# usb-fanctl.net
KiCad netlist of a schematic drawn in EAGLE
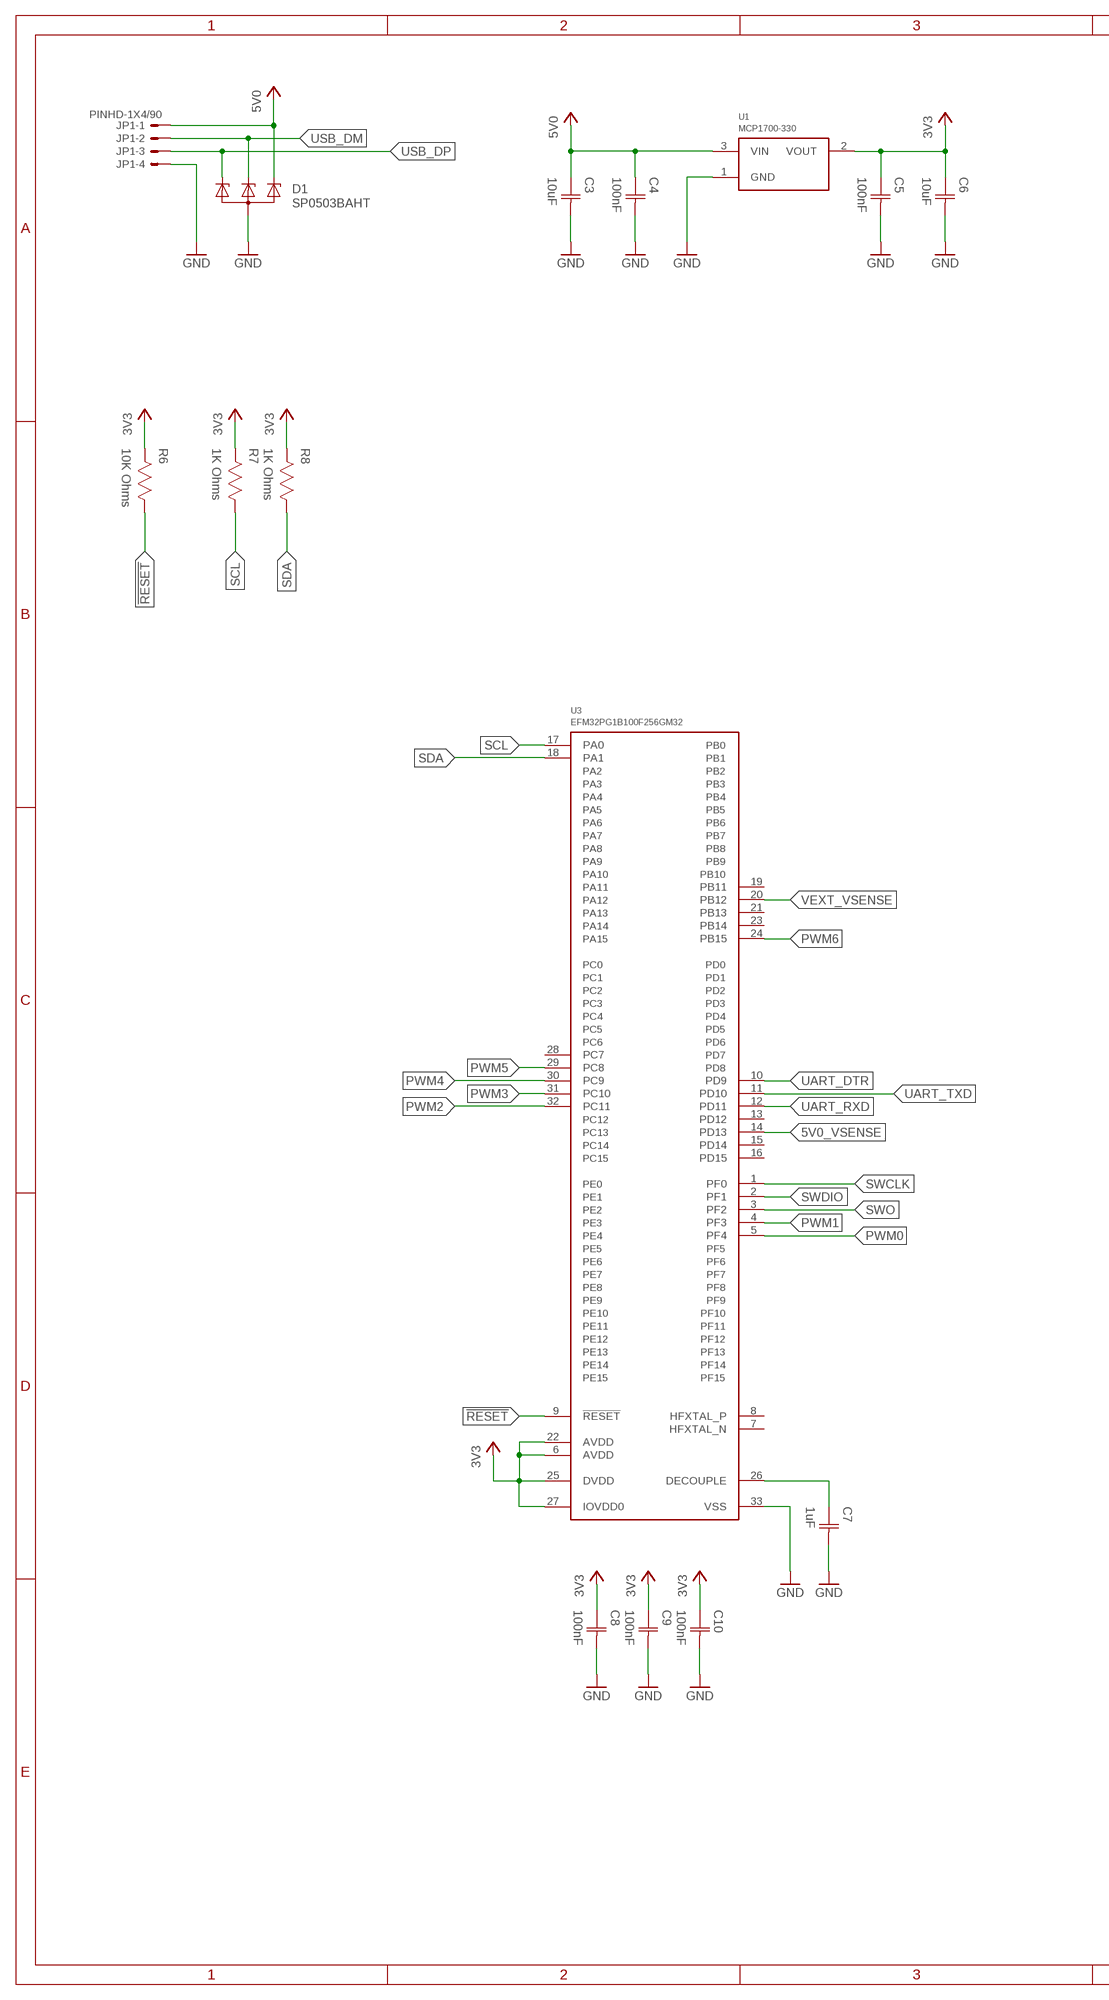
[diagram p0: schematic, sheet 1, part 1 of 2]
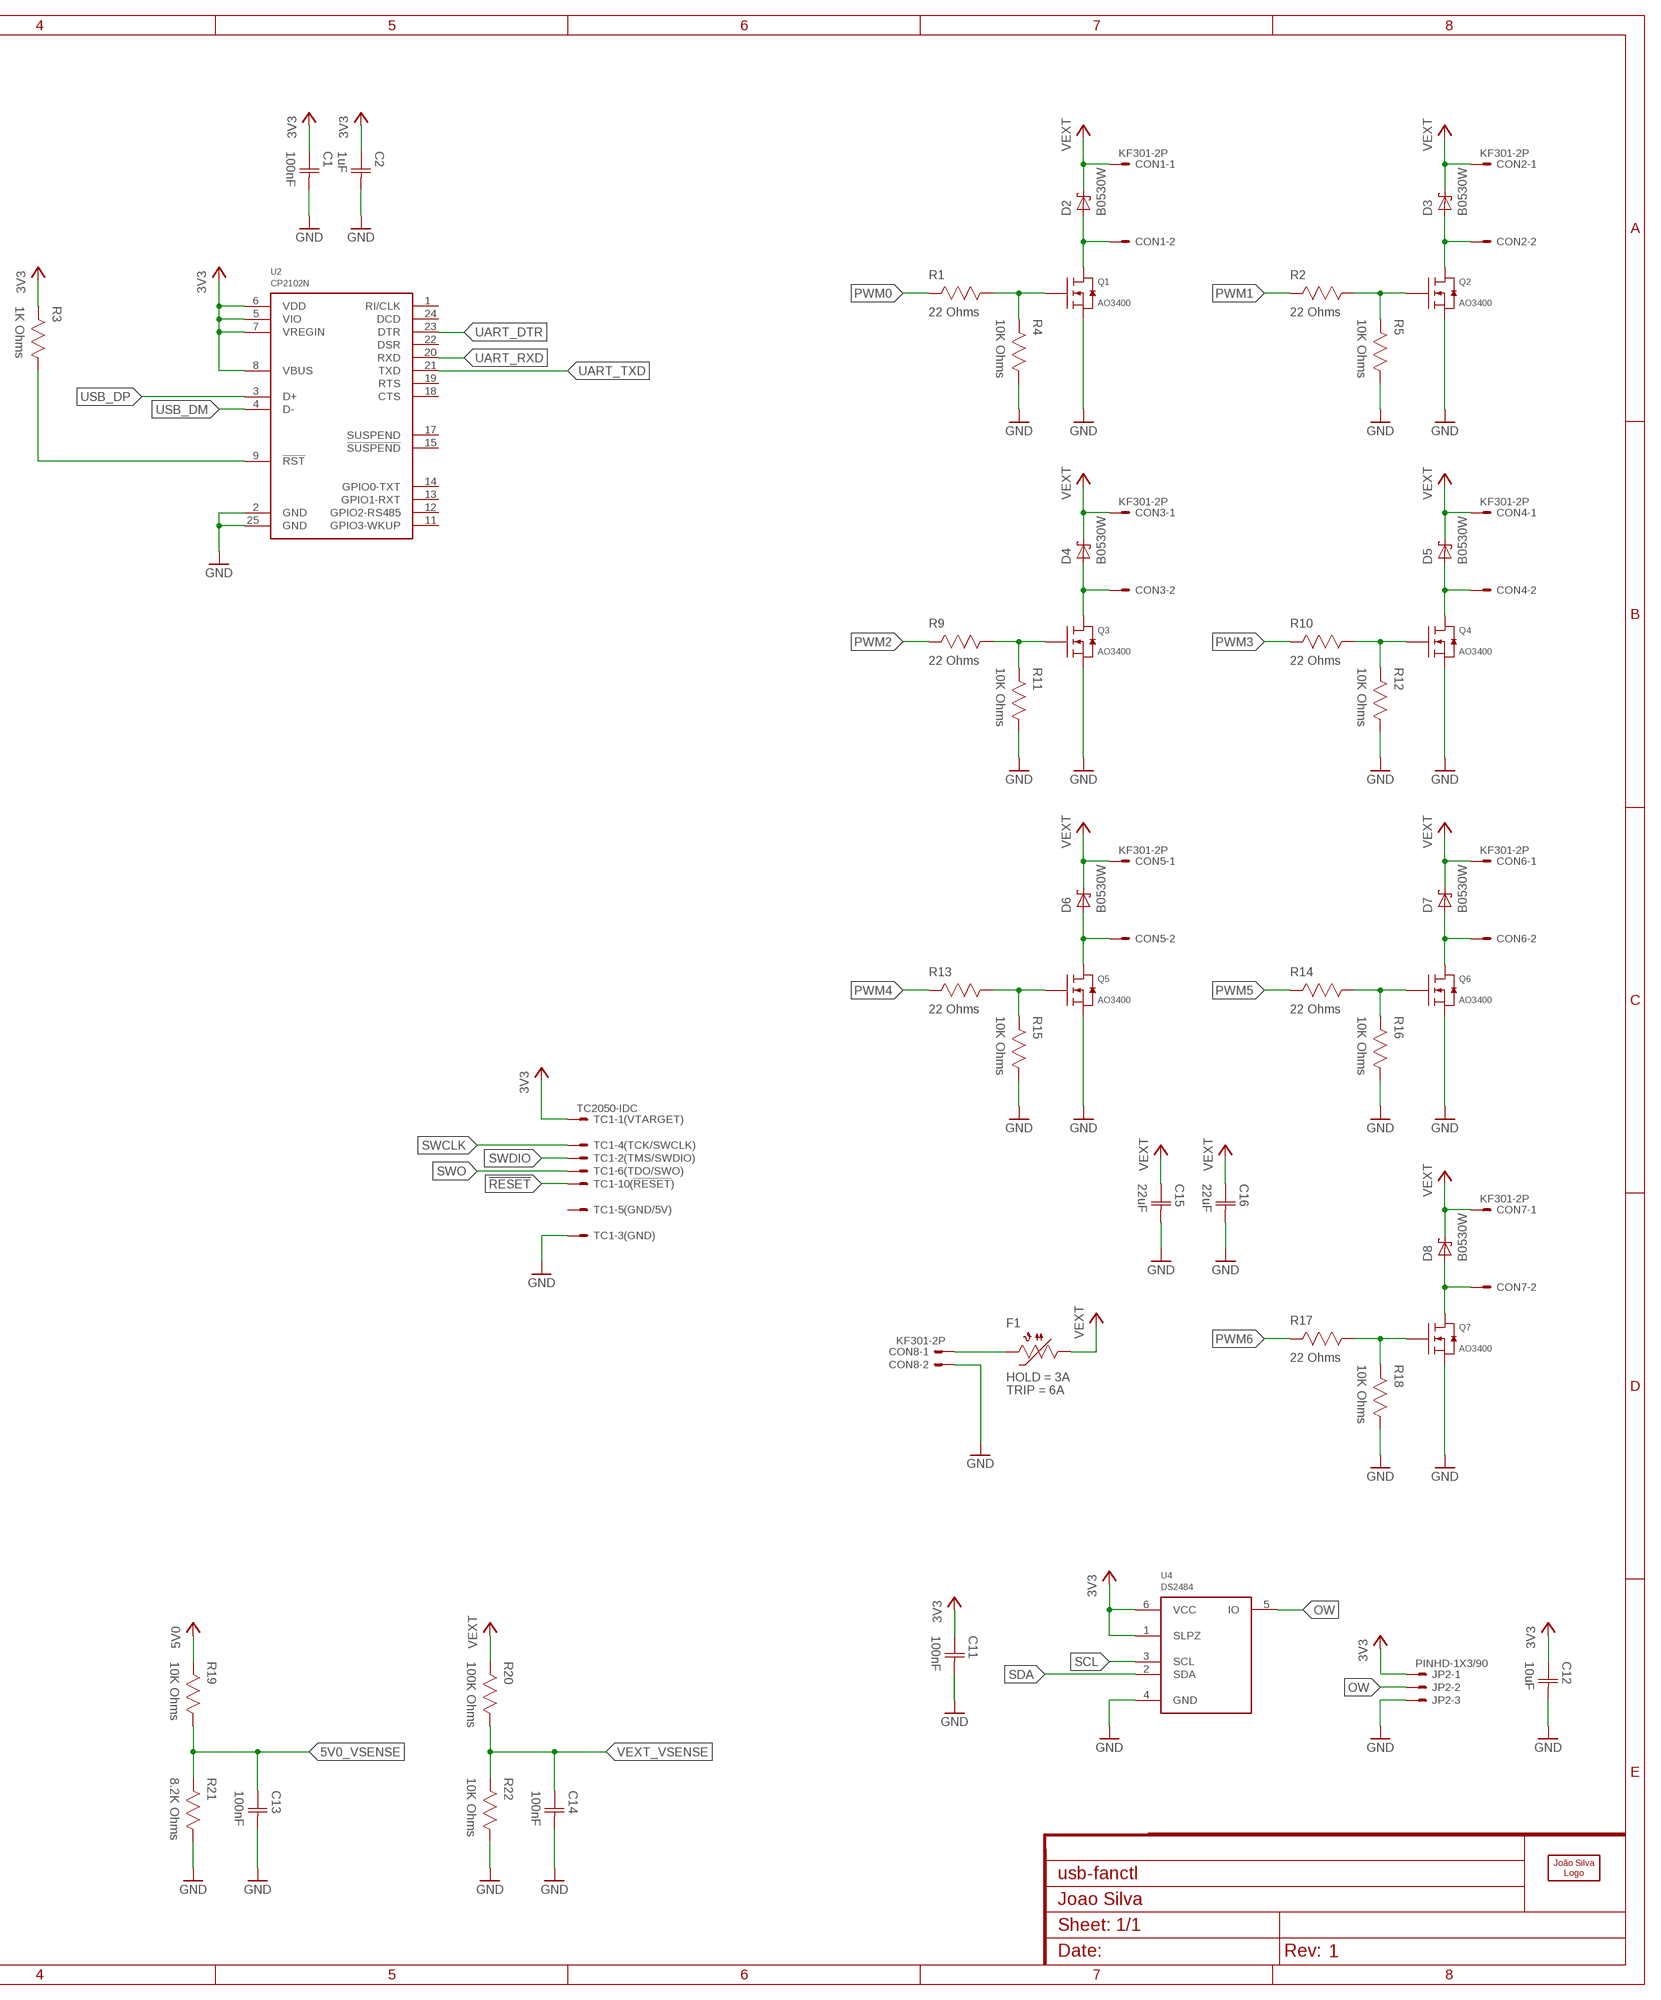
[diagram p1: schematic, sheet 1, part 2 of 2]

(export (version "E")
  (design (tool "Eeschema 10.0.6"))
  (components
    (comp (ref "C1")
      (value "100nF")
      (footprint "eagle-import:CAP0402")
      (libsource (lib "eagle-import") (part "CAPACITOR-0402"))
    )
    (comp (ref "C2")
      (value "1uF")
      (footprint "eagle-import:CAP0402")
      (libsource (lib "eagle-import") (part "CAPACITOR-0402"))
    )
    (comp (ref "C3")
      (value "10uF")
      (footprint "eagle-import:CAP0603")
      (libsource (lib "eagle-import") (part "CAPACITOR-0603"))
    )
    (comp (ref "C4")
      (value "100nF")
      (footprint "eagle-import:CAP0402")
      (libsource (lib "eagle-import") (part "CAPACITOR-0402"))
    )
    (comp (ref "C5")
      (value "100nF")
      (footprint "eagle-import:CAP0402")
      (libsource (lib "eagle-import") (part "CAPACITOR-0402"))
    )
    (comp (ref "C6")
      (value "10uF")
      (footprint "eagle-import:CAP0603")
      (libsource (lib "eagle-import") (part "CAPACITOR-0603"))
    )
    (comp (ref "C7")
      (value "1uF")
      (footprint "eagle-import:CAP0402")
      (libsource (lib "eagle-import") (part "CAPACITOR-0402"))
    )
    (comp (ref "C8")
      (value "100nF")
      (footprint "eagle-import:CAP0402")
      (libsource (lib "eagle-import") (part "CAPACITOR-0402"))
    )
    (comp (ref "C9")
      (value "100nF")
      (footprint "eagle-import:CAP0402")
      (libsource (lib "eagle-import") (part "CAPACITOR-0402"))
    )
    (comp (ref "C10")
      (value "100nF")
      (footprint "eagle-import:CAP0402")
      (libsource (lib "eagle-import") (part "CAPACITOR-0402"))
    )
    (comp (ref "C11")
      (value "100nF")
      (footprint "eagle-import:CAP0402")
      (libsource (lib "eagle-import") (part "CAPACITOR-0402"))
    )
    (comp (ref "C12")
      (value "10uF")
      (footprint "eagle-import:CAP0603")
      (libsource (lib "eagle-import") (part "CAPACITOR-0603"))
    )
    (comp (ref "C13")
      (value "100nF")
      (footprint "eagle-import:CAP0402")
      (libsource (lib "eagle-import") (part "CAPACITOR-0402"))
    )
    (comp (ref "C14")
      (value "100nF")
      (footprint "eagle-import:CAP0402")
      (libsource (lib "eagle-import") (part "CAPACITOR-0402"))
    )
    (comp (ref "C15")
      (value "22uF")
      (footprint "eagle-import:CAP1206")
      (libsource (lib "eagle-import") (part "CAPACITOR-1206"))
    )
    (comp (ref "C16")
      (value "22uF")
      (footprint "eagle-import:CAP1206")
      (libsource (lib "eagle-import") (part "CAPACITOR-1206"))
    )
    (comp (ref "CON1")
      (value "KF301-2P")
      (footprint "eagle-import:KF301-2P")
      (libsource (lib "eagle-import") (part "KF301-2P"))
    )
    (comp (ref "CON2")
      (value "KF301-2P")
      (footprint "eagle-import:KF301-2P")
      (libsource (lib "eagle-import") (part "KF301-2P"))
    )
    (comp (ref "CON3")
      (value "KF301-2P")
      (footprint "eagle-import:KF301-2P")
      (libsource (lib "eagle-import") (part "KF301-2P"))
    )
    (comp (ref "CON4")
      (value "KF301-2P")
      (footprint "eagle-import:KF301-2P")
      (libsource (lib "eagle-import") (part "KF301-2P"))
    )
    (comp (ref "CON5")
      (value "KF301-2P")
      (footprint "eagle-import:KF301-2P")
      (libsource (lib "eagle-import") (part "KF301-2P"))
    )
    (comp (ref "CON6")
      (value "KF301-2P")
      (footprint "eagle-import:KF301-2P")
      (libsource (lib "eagle-import") (part "KF301-2P"))
    )
    (comp (ref "CON7")
      (value "KF301-2P")
      (footprint "eagle-import:KF301-2P")
      (libsource (lib "eagle-import") (part "KF301-2P"))
    )
    (comp (ref "CON8")
      (value "KF301-2P")
      (footprint "eagle-import:KF301-2P")
      (libsource (lib "eagle-import") (part "KF301-2P"))
    )
    (comp (ref "D1")
      (value "SP0503BAHT")
      (footprint "eagle-import:SOT143")
      (libsource (lib "eagle-import") (part "SP0503BAHT"))
    )
    (comp (ref "D2")
      (value "B0530W")
      (footprint "eagle-import:SOD-123")
      (libsource (lib "eagle-import") (part "B0530W"))
    )
    (comp (ref "D3")
      (value "B0530W")
      (footprint "eagle-import:SOD-123")
      (libsource (lib "eagle-import") (part "B0530W"))
    )
    (comp (ref "D4")
      (value "B0530W")
      (footprint "eagle-import:SOD-123")
      (libsource (lib "eagle-import") (part "B0530W"))
    )
    (comp (ref "D5")
      (value "B0530W")
      (footprint "eagle-import:SOD-123")
      (libsource (lib "eagle-import") (part "B0530W"))
    )
    (comp (ref "D6")
      (value "B0530W")
      (footprint "eagle-import:SOD-123")
      (libsource (lib "eagle-import") (part "B0530W"))
    )
    (comp (ref "D7")
      (value "B0530W")
      (footprint "eagle-import:SOD-123")
      (libsource (lib "eagle-import") (part "B0530W"))
    )
    (comp (ref "D8")
      (value "B0530W")
      (footprint "eagle-import:SOD-123")
      (libsource (lib "eagle-import") (part "B0530W"))
    )
    (comp (ref "F1")
      (value "PTC1206")
      (footprint "eagle-import:1206")
      (fields (field (name "HOLD") "3A") (field (name "TRIP") "6A"))
      (libsource (lib "eagle-import") (part "PTC1206"))
    )
    (comp (ref "JP1")
      (value "PINHD-1X4/90")
      (footprint "eagle-import:1X04_90")
      (libsource (lib "eagle-import") (part "PINHD-1X4/90"))
    )
    (comp (ref "JP2")
      (value "PINHD-1X3/90")
      (footprint "eagle-import:1X03_90")
      (libsource (lib "eagle-import") (part "PINHD-1X3/90"))
    )
    (comp (ref "LOGO1")
      (value "JS-5MM")
      (footprint "eagle-import:JS_5MM")
      (libsource (lib "eagle-import") (part "JS-5MM"))
    )
    (comp (ref "Q1")
      (value "AO3400")
      (footprint "eagle-import:SOT23")
      (libsource (lib "eagle-import") (part "AO3400"))
    )
    (comp (ref "Q2")
      (value "AO3400")
      (footprint "eagle-import:SOT23")
      (libsource (lib "eagle-import") (part "AO3400"))
    )
    (comp (ref "Q3")
      (value "AO3400")
      (footprint "eagle-import:SOT23")
      (libsource (lib "eagle-import") (part "AO3400"))
    )
    (comp (ref "Q4")
      (value "AO3400")
      (footprint "eagle-import:SOT23")
      (libsource (lib "eagle-import") (part "AO3400"))
    )
    (comp (ref "Q5")
      (value "AO3400")
      (footprint "eagle-import:SOT23")
      (libsource (lib "eagle-import") (part "AO3400"))
    )
    (comp (ref "Q6")
      (value "AO3400")
      (footprint "eagle-import:SOT23")
      (libsource (lib "eagle-import") (part "AO3400"))
    )
    (comp (ref "Q7")
      (value "AO3400")
      (footprint "eagle-import:SOT23")
      (libsource (lib "eagle-import") (part "AO3400"))
    )
    (comp (ref "R1")
      (value "22 Ohms")
      (footprint "eagle-import:RES0402")
      (libsource (lib "eagle-import") (part "RESISTOR-0402"))
    )
    (comp (ref "R2")
      (value "22 Ohms")
      (footprint "eagle-import:RES0402")
      (libsource (lib "eagle-import") (part "RESISTOR-0402"))
    )
    (comp (ref "R3")
      (value "1K Ohms")
      (footprint "eagle-import:RES0402")
      (libsource (lib "eagle-import") (part "RESISTOR-0402"))
    )
    (comp (ref "R4")
      (value "10K Ohms")
      (footprint "eagle-import:RES0402")
      (libsource (lib "eagle-import") (part "RESISTOR-0402"))
    )
    (comp (ref "R5")
      (value "10K Ohms")
      (footprint "eagle-import:RES0402")
      (libsource (lib "eagle-import") (part "RESISTOR-0402"))
    )
    (comp (ref "R6")
      (value "10K Ohms")
      (footprint "eagle-import:RES0402")
      (libsource (lib "eagle-import") (part "RESISTOR-0402"))
    )
    (comp (ref "R7")
      (value "1K Ohms")
      (footprint "eagle-import:RES0402")
      (libsource (lib "eagle-import") (part "RESISTOR-0402"))
    )
    (comp (ref "R8")
      (value "1K Ohms")
      (footprint "eagle-import:RES0402")
      (libsource (lib "eagle-import") (part "RESISTOR-0402"))
    )
    (comp (ref "R9")
      (value "22 Ohms")
      (footprint "eagle-import:RES0402")
      (libsource (lib "eagle-import") (part "RESISTOR-0402"))
    )
    (comp (ref "R10")
      (value "22 Ohms")
      (footprint "eagle-import:RES0402")
      (libsource (lib "eagle-import") (part "RESISTOR-0402"))
    )
    (comp (ref "R11")
      (value "10K Ohms")
      (footprint "eagle-import:RES0402")
      (libsource (lib "eagle-import") (part "RESISTOR-0402"))
    )
    (comp (ref "R12")
      (value "10K Ohms")
      (footprint "eagle-import:RES0402")
      (libsource (lib "eagle-import") (part "RESISTOR-0402"))
    )
    (comp (ref "R13")
      (value "22 Ohms")
      (footprint "eagle-import:RES0402")
      (libsource (lib "eagle-import") (part "RESISTOR-0402"))
    )
    (comp (ref "R14")
      (value "22 Ohms")
      (footprint "eagle-import:RES0402")
      (libsource (lib "eagle-import") (part "RESISTOR-0402"))
    )
    (comp (ref "R15")
      (value "10K Ohms")
      (footprint "eagle-import:RES0402")
      (libsource (lib "eagle-import") (part "RESISTOR-0402"))
    )
    (comp (ref "R16")
      (value "10K Ohms")
      (footprint "eagle-import:RES0402")
      (libsource (lib "eagle-import") (part "RESISTOR-0402"))
    )
    (comp (ref "R17")
      (value "22 Ohms")
      (footprint "eagle-import:RES0402")
      (libsource (lib "eagle-import") (part "RESISTOR-0402"))
    )
    (comp (ref "R18")
      (value "10K Ohms")
      (footprint "eagle-import:RES0402")
      (libsource (lib "eagle-import") (part "RESISTOR-0402"))
    )
    (comp (ref "R19")
      (value "10K Ohms")
      (footprint "eagle-import:RES0402")
      (libsource (lib "eagle-import") (part "RESISTOR-0402"))
    )
    (comp (ref "R20")
      (value "100K Ohms")
      (footprint "eagle-import:RES0402")
      (libsource (lib "eagle-import") (part "RESISTOR-0402"))
    )
    (comp (ref "R21")
      (value "8.2K Ohms")
      (footprint "eagle-import:RES0402")
      (libsource (lib "eagle-import") (part "RESISTOR-0402"))
    )
    (comp (ref "R22")
      (value "10K Ohms")
      (footprint "eagle-import:RES0402")
      (libsource (lib "eagle-import") (part "RESISTOR-0402"))
    )
    (comp (ref "TC1")
      (value "TC2050-IDC")
      (footprint "eagle-import:TC2050-IDC")
      (libsource (lib "eagle-import") (part "TC2050-IDC"))
    )
    (comp (ref "U1")
      (value "MCP1700-330")
      (footprint "eagle-import:SOT23")
      (libsource (lib "eagle-import") (part "MCP1700-330"))
    )
    (comp (ref "U2")
      (value "CP2102N")
      (footprint "eagle-import:QFN24")
      (libsource (lib "eagle-import") (part "CP2102N"))
    )
    (comp (ref "U3")
      (value "EFM32PG1B100F256GM32")
      (footprint "eagle-import:QFN32_0.5P_JPG")
      (libsource (lib "eagle-import") (part "EFM32PG1B100FM32256G"))
    )
    (comp (ref "U4")
      (value "DS2484")
      (footprint "eagle-import:SOT23-6")
      (libsource (lib "eagle-import") (part "DS2484"))
    )
  )
  (nets
    (net (code "1") (name "/~{RESET}") (class "Default")
      (node (ref "R6") (pin "1") (pinfunction "1_1") (pintype "passive"))
      (node (ref "TC1") (pin "10") (pinfunction "S_10") (pintype "passive"))
      (node (ref "U3") (pin "9") (pinfunction "~{RESET}_9") (pintype "bidirectional"))
    )
    (net (code "2") (name "3V3") (class "Default")
      (node (ref "C1") (pin "1") (pinfunction "C1_1") (pintype "passive"))
      (node (ref "C10") (pin "1") (pinfunction "C1_1") (pintype "passive"))
      (node (ref "C11") (pin "1") (pinfunction "C1_1") (pintype "passive"))
      (node (ref "C12") (pin "1") (pinfunction "C1_1") (pintype "passive"))
      (node (ref "C2") (pin "1") (pinfunction "C1_1") (pintype "passive"))
      (node (ref "C5") (pin "1") (pinfunction "C1_1") (pintype "passive"))
      (node (ref "C6") (pin "1") (pinfunction "C1_1") (pintype "passive"))
      (node (ref "C8") (pin "1") (pinfunction "C1_1") (pintype "passive"))
      (node (ref "C9") (pin "1") (pinfunction "C1_1") (pintype "passive"))
      (node (ref "JP2") (pin "1") (pinfunction "S_1") (pintype "passive"))
      (node (ref "R3") (pin "2") (pinfunction "2_2") (pintype "passive"))
      (node (ref "R6") (pin "2") (pinfunction "2_2") (pintype "passive"))
      (node (ref "R7") (pin "2") (pinfunction "2_2") (pintype "passive"))
      (node (ref "R8") (pin "2") (pinfunction "2_2") (pintype "passive"))
      (node (ref "TC1") (pin "1") (pinfunction "S_1") (pintype "passive"))
      (node (ref "U1") (pin "2") (pinfunction "VOUT_2") (pintype "bidirectional"))
      (node (ref "U2") (pin "5") (pinfunction "VIO_5") (pintype "bidirectional"))
      (node (ref "U2") (pin "6") (pinfunction "VDD_6") (pintype "bidirectional"))
      (node (ref "U2") (pin "7") (pinfunction "VREGIN_7") (pintype "bidirectional"))
      (node (ref "U2") (pin "8") (pinfunction "VBUS_8") (pintype "bidirectional"))
      (node (ref "U3") (pin "22") (pinfunction "AVDD_22") (pintype "bidirectional"))
      (node (ref "U3") (pin "25") (pinfunction "DVDD_25") (pintype "bidirectional"))
      (node (ref "U3") (pin "27") (pinfunction "IOVDD0_27") (pintype "bidirectional"))
      (node (ref "U3") (pin "6") (pinfunction "AVDD_6") (pintype "bidirectional"))
      (node (ref "U4") (pin "1") (pinfunction "SLPZ_1") (pintype "bidirectional"))
      (node (ref "U4") (pin "6") (pinfunction "VCC_6") (pintype "bidirectional"))
    )
    (net (code "3") (name "5V0") (class "Default")
      (node (ref "C3") (pin "1") (pinfunction "C1_1") (pintype "passive"))
      (node (ref "C4") (pin "1") (pinfunction "C1_1") (pintype "passive"))
      (node (ref "D1") (pin "4") (pinfunction "C3_4") (pintype "bidirectional"))
      (node (ref "JP1") (pin "1") (pinfunction "S_1") (pintype "passive"))
      (node (ref "R19") (pin "2") (pinfunction "2_2") (pintype "passive"))
      (node (ref "U1") (pin "3") (pinfunction "VIN_3") (pintype "bidirectional"))
    )
    (net (code "4") (name "5V0_VSENSE") (class "Default")
      (node (ref "C13") (pin "1") (pinfunction "C1_1") (pintype "passive"))
      (node (ref "R19") (pin "1") (pinfunction "1_1") (pintype "passive"))
      (node (ref "R21") (pin "2") (pinfunction "2_2") (pintype "passive"))
      (node (ref "U3") (pin "14") (pinfunction "PD13_14") (pintype "bidirectional"))
    )
    (net (code "5") (name "GND") (class "Default")
      (node (ref "C1") (pin "2") (pinfunction "C2_2") (pintype "passive"))
      (node (ref "C10") (pin "2") (pinfunction "C2_2") (pintype "passive"))
      (node (ref "C11") (pin "2") (pinfunction "C2_2") (pintype "passive"))
      (node (ref "C12") (pin "2") (pinfunction "C2_2") (pintype "passive"))
      (node (ref "C13") (pin "2") (pinfunction "C2_2") (pintype "passive"))
      (node (ref "C14") (pin "2") (pinfunction "C2_2") (pintype "passive"))
      (node (ref "C15") (pin "2") (pinfunction "C2_2") (pintype "passive"))
      (node (ref "C16") (pin "2") (pinfunction "C2_2") (pintype "passive"))
      (node (ref "C2") (pin "2") (pinfunction "C2_2") (pintype "passive"))
      (node (ref "C3") (pin "2") (pinfunction "C2_2") (pintype "passive"))
      (node (ref "C4") (pin "2") (pinfunction "C2_2") (pintype "passive"))
      (node (ref "C5") (pin "2") (pinfunction "C2_2") (pintype "passive"))
      (node (ref "C6") (pin "2") (pinfunction "C2_2") (pintype "passive"))
      (node (ref "C7") (pin "2") (pinfunction "C2_2") (pintype "passive"))
      (node (ref "C8") (pin "2") (pinfunction "C2_2") (pintype "passive"))
      (node (ref "C9") (pin "2") (pinfunction "C2_2") (pintype "passive"))
      (node (ref "CON8") (pin "2") (pinfunction "S_2") (pintype "passive"))
      (node (ref "D1") (pin "1") (pinfunction "A_1") (pintype "bidirectional"))
      (node (ref "JP1") (pin "4") (pinfunction "S_4") (pintype "passive"))
      (node (ref "JP2") (pin "3") (pinfunction "S_3") (pintype "passive"))
      (node (ref "Q1") (pin "2") (pinfunction "S_2") (pintype "passive"))
      (node (ref "Q2") (pin "2") (pinfunction "S_2") (pintype "passive"))
      (node (ref "Q3") (pin "2") (pinfunction "S_2") (pintype "passive"))
      (node (ref "Q4") (pin "2") (pinfunction "S_2") (pintype "passive"))
      (node (ref "Q5") (pin "2") (pinfunction "S_2") (pintype "passive"))
      (node (ref "Q6") (pin "2") (pinfunction "S_2") (pintype "passive"))
      (node (ref "Q7") (pin "2") (pinfunction "S_2") (pintype "passive"))
      (node (ref "R11") (pin "1") (pinfunction "1_1") (pintype "passive"))
      (node (ref "R12") (pin "1") (pinfunction "1_1") (pintype "passive"))
      (node (ref "R15") (pin "1") (pinfunction "1_1") (pintype "passive"))
      (node (ref "R16") (pin "1") (pinfunction "1_1") (pintype "passive"))
      (node (ref "R18") (pin "1") (pinfunction "1_1") (pintype "passive"))
      (node (ref "R21") (pin "1") (pinfunction "1_1") (pintype "passive"))
      (node (ref "R22") (pin "1") (pinfunction "1_1") (pintype "passive"))
      (node (ref "R4") (pin "1") (pinfunction "1_1") (pintype "passive"))
      (node (ref "R5") (pin "1") (pinfunction "1_1") (pintype "passive"))
      (node (ref "TC1") (pin "3") (pinfunction "S_3") (pintype "passive"))
      (node (ref "U1") (pin "1") (pinfunction "GND_1") (pintype "bidirectional"))
      (node (ref "U2") (pin "2") (pinfunction "GND_2") (pintype "bidirectional"))
      (node (ref "U2") (pin "25") (pinfunction "GND_25") (pintype "bidirectional"))
      (node (ref "U3") (pin "33") (pinfunction "VSS_33") (pintype "bidirectional"))
      (node (ref "U4") (pin "4") (pinfunction "GND_4") (pintype "bidirectional"))
    )
    (net (code "6") (name "Net-(C7-C1)") (class "Default")
      (node (ref "C7") (pin "1") (pinfunction "C1_1") (pintype "passive"))
      (node (ref "U3") (pin "26") (pinfunction "DECOUPLE_26") (pintype "bidirectional"))
    )
    (net (code "7") (name "Net-(CON1B-S)") (class "Default")
      (node (ref "CON1") (pin "2") (pinfunction "S_2") (pintype "passive"))
      (node (ref "D2") (pin "A") (pinfunction "A_A") (pintype "passive"))
      (node (ref "Q1") (pin "3") (pinfunction "D_3") (pintype "passive"))
    )
    (net (code "8") (name "Net-(CON2B-S)") (class "Default")
      (node (ref "CON2") (pin "2") (pinfunction "S_2") (pintype "passive"))
      (node (ref "D3") (pin "A") (pinfunction "A_A") (pintype "passive"))
      (node (ref "Q2") (pin "3") (pinfunction "D_3") (pintype "passive"))
    )
    (net (code "9") (name "Net-(CON3B-S)") (class "Default")
      (node (ref "CON3") (pin "2") (pinfunction "S_2") (pintype "passive"))
      (node (ref "D4") (pin "A") (pinfunction "A_A") (pintype "passive"))
      (node (ref "Q3") (pin "3") (pinfunction "D_3") (pintype "passive"))
    )
    (net (code "10") (name "Net-(CON4B-S)") (class "Default")
      (node (ref "CON4") (pin "2") (pinfunction "S_2") (pintype "passive"))
      (node (ref "D5") (pin "A") (pinfunction "A_A") (pintype "passive"))
      (node (ref "Q4") (pin "3") (pinfunction "D_3") (pintype "passive"))
    )
    (net (code "11") (name "Net-(CON5B-S)") (class "Default")
      (node (ref "CON5") (pin "2") (pinfunction "S_2") (pintype "passive"))
      (node (ref "D6") (pin "A") (pinfunction "A_A") (pintype "passive"))
      (node (ref "Q5") (pin "3") (pinfunction "D_3") (pintype "passive"))
    )
    (net (code "12") (name "Net-(CON6B-S)") (class "Default")
      (node (ref "CON6") (pin "2") (pinfunction "S_2") (pintype "passive"))
      (node (ref "D7") (pin "A") (pinfunction "A_A") (pintype "passive"))
      (node (ref "Q6") (pin "3") (pinfunction "D_3") (pintype "passive"))
    )
    (net (code "13") (name "Net-(CON7B-S)") (class "Default")
      (node (ref "CON7") (pin "2") (pinfunction "S_2") (pintype "passive"))
      (node (ref "D8") (pin "A") (pinfunction "A_A") (pintype "passive"))
      (node (ref "Q7") (pin "3") (pinfunction "D_3") (pintype "passive"))
    )
    (net (code "14") (name "Net-(CON8A-S)") (class "Default")
      (node (ref "CON8") (pin "1") (pinfunction "S_1") (pintype "passive"))
      (node (ref "F1") (pin "2") (pinfunction "2_2") (pintype "passive"))
    )
    (net (code "15") (name "Net-(Q1-G)") (class "Default")
      (node (ref "Q1") (pin "1") (pinfunction "G_1") (pintype "passive"))
      (node (ref "R1") (pin "1") (pinfunction "1_1") (pintype "passive"))
      (node (ref "R4") (pin "2") (pinfunction "2_2") (pintype "passive"))
    )
    (net (code "16") (name "Net-(Q2-G)") (class "Default")
      (node (ref "Q2") (pin "1") (pinfunction "G_1") (pintype "passive"))
      (node (ref "R2") (pin "1") (pinfunction "1_1") (pintype "passive"))
      (node (ref "R5") (pin "2") (pinfunction "2_2") (pintype "passive"))
    )
    (net (code "17") (name "Net-(Q3-G)") (class "Default")
      (node (ref "Q3") (pin "1") (pinfunction "G_1") (pintype "passive"))
      (node (ref "R11") (pin "2") (pinfunction "2_2") (pintype "passive"))
      (node (ref "R9") (pin "1") (pinfunction "1_1") (pintype "passive"))
    )
    (net (code "18") (name "Net-(Q4-G)") (class "Default")
      (node (ref "Q4") (pin "1") (pinfunction "G_1") (pintype "passive"))
      (node (ref "R10") (pin "1") (pinfunction "1_1") (pintype "passive"))
      (node (ref "R12") (pin "2") (pinfunction "2_2") (pintype "passive"))
    )
    (net (code "19") (name "Net-(Q5-G)") (class "Default")
      (node (ref "Q5") (pin "1") (pinfunction "G_1") (pintype "passive"))
      (node (ref "R13") (pin "1") (pinfunction "1_1") (pintype "passive"))
      (node (ref "R15") (pin "2") (pinfunction "2_2") (pintype "passive"))
    )
    (net (code "20") (name "Net-(Q6-G)") (class "Default")
      (node (ref "Q6") (pin "1") (pinfunction "G_1") (pintype "passive"))
      (node (ref "R14") (pin "1") (pinfunction "1_1") (pintype "passive"))
      (node (ref "R16") (pin "2") (pinfunction "2_2") (pintype "passive"))
    )
    (net (code "21") (name "Net-(Q7-G)") (class "Default")
      (node (ref "Q7") (pin "1") (pinfunction "G_1") (pintype "passive"))
      (node (ref "R17") (pin "1") (pinfunction "1_1") (pintype "passive"))
      (node (ref "R18") (pin "2") (pinfunction "2_2") (pintype "passive"))
    )
    (net (code "22") (name "Net-(U2-~{RST})") (class "Default")
      (node (ref "R3") (pin "1") (pinfunction "1_1") (pintype "passive"))
      (node (ref "U2") (pin "9") (pinfunction "~{RST}_9") (pintype "bidirectional"))
    )
    (net (code "23") (name "OW") (class "Default")
      (node (ref "JP2") (pin "2") (pinfunction "S_2") (pintype "passive"))
      (node (ref "U4") (pin "5") (pinfunction "IO_5") (pintype "bidirectional"))
    )
    (net (code "24") (name "PWM0") (class "Default")
      (node (ref "R1") (pin "2") (pinfunction "2_2") (pintype "passive"))
      (node (ref "U3") (pin "5") (pinfunction "PF4_5") (pintype "bidirectional"))
    )
    (net (code "25") (name "PWM1") (class "Default")
      (node (ref "R2") (pin "2") (pinfunction "2_2") (pintype "passive"))
      (node (ref "U3") (pin "4") (pinfunction "PF3_4") (pintype "bidirectional"))
    )
    (net (code "26") (name "PWM2") (class "Default")
      (node (ref "R9") (pin "2") (pinfunction "2_2") (pintype "passive"))
      (node (ref "U3") (pin "32") (pinfunction "PC11_32") (pintype "bidirectional"))
    )
    (net (code "27") (name "PWM3") (class "Default")
      (node (ref "R10") (pin "2") (pinfunction "2_2") (pintype "passive"))
      (node (ref "U3") (pin "31") (pinfunction "PC10_31") (pintype "bidirectional"))
    )
    (net (code "28") (name "PWM4") (class "Default")
      (node (ref "R13") (pin "2") (pinfunction "2_2") (pintype "passive"))
      (node (ref "U3") (pin "30") (pinfunction "PC9_30") (pintype "bidirectional"))
    )
    (net (code "29") (name "PWM5") (class "Default")
      (node (ref "R14") (pin "2") (pinfunction "2_2") (pintype "passive"))
      (node (ref "U3") (pin "29") (pinfunction "PC8_29") (pintype "bidirectional"))
    )
    (net (code "30") (name "PWM6") (class "Default")
      (node (ref "R17") (pin "2") (pinfunction "2_2") (pintype "passive"))
      (node (ref "U3") (pin "24") (pinfunction "PB15_24") (pintype "bidirectional"))
    )
    (net (code "31") (name "SCL") (class "Default")
      (node (ref "R7") (pin "1") (pinfunction "1_1") (pintype "passive"))
      (node (ref "U3") (pin "17") (pinfunction "PA0_17") (pintype "bidirectional"))
      (node (ref "U4") (pin "3") (pinfunction "SCL_3") (pintype "bidirectional"))
    )
    (net (code "32") (name "SDA") (class "Default")
      (node (ref "R8") (pin "1") (pinfunction "1_1") (pintype "passive"))
      (node (ref "U3") (pin "18") (pinfunction "PA1_18") (pintype "bidirectional"))
      (node (ref "U4") (pin "2") (pinfunction "SDA_2") (pintype "bidirectional"))
    )
    (net (code "33") (name "SWCLK") (class "Default")
      (node (ref "TC1") (pin "4") (pinfunction "S_4") (pintype "passive"))
      (node (ref "U3") (pin "1") (pinfunction "PF0_1") (pintype "bidirectional"))
    )
    (net (code "34") (name "SWDIO") (class "Default")
      (node (ref "TC1") (pin "2") (pinfunction "S_2") (pintype "passive"))
      (node (ref "U3") (pin "2") (pinfunction "PF1_2") (pintype "bidirectional"))
    )
    (net (code "35") (name "SWO") (class "Default")
      (node (ref "TC1") (pin "6") (pinfunction "S_6") (pintype "passive"))
      (node (ref "U3") (pin "3") (pinfunction "PF2_3") (pintype "bidirectional"))
    )
    (net (code "36") (name "UART_DTR") (class "Default")
      (node (ref "U2") (pin "23") (pinfunction "DTR_23") (pintype "bidirectional"))
      (node (ref "U3") (pin "10") (pinfunction "PD9_10") (pintype "bidirectional"))
    )
    (net (code "37") (name "UART_RXD") (class "Default")
      (node (ref "U2") (pin "20") (pinfunction "RXD_20") (pintype "bidirectional"))
      (node (ref "U3") (pin "12") (pinfunction "PD11_12") (pintype "bidirectional"))
    )
    (net (code "38") (name "UART_TXD") (class "Default")
      (node (ref "U2") (pin "21") (pinfunction "TXD_21") (pintype "bidirectional"))
      (node (ref "U3") (pin "11") (pinfunction "PD10_11") (pintype "bidirectional"))
    )
    (net (code "39") (name "USB_DM") (class "Default")
      (node (ref "D1") (pin "3") (pinfunction "C2_3") (pintype "bidirectional"))
      (node (ref "JP1") (pin "2") (pinfunction "S_2") (pintype "passive"))
      (node (ref "U2") (pin "4") (pinfunction "D-_4") (pintype "bidirectional"))
    )
    (net (code "40") (name "USB_DP") (class "Default")
      (node (ref "D1") (pin "2") (pinfunction "C1_2") (pintype "bidirectional"))
      (node (ref "JP1") (pin "3") (pinfunction "S_3") (pintype "passive"))
      (node (ref "U2") (pin "3") (pinfunction "D+_3") (pintype "bidirectional"))
    )
    (net (code "41") (name "VEXT") (class "Default")
      (node (ref "C15") (pin "1") (pinfunction "C1_1") (pintype "passive"))
      (node (ref "C16") (pin "1") (pinfunction "C1_1") (pintype "passive"))
      (node (ref "CON1") (pin "1") (pinfunction "S_1") (pintype "passive"))
      (node (ref "CON2") (pin "1") (pinfunction "S_1") (pintype "passive"))
      (node (ref "CON3") (pin "1") (pinfunction "S_1") (pintype "passive"))
      (node (ref "CON4") (pin "1") (pinfunction "S_1") (pintype "passive"))
      (node (ref "CON5") (pin "1") (pinfunction "S_1") (pintype "passive"))
      (node (ref "CON6") (pin "1") (pinfunction "S_1") (pintype "passive"))
      (node (ref "CON7") (pin "1") (pinfunction "S_1") (pintype "passive"))
      (node (ref "D2") (pin "C") (pinfunction "C_C") (pintype "passive"))
      (node (ref "D3") (pin "C") (pinfunction "C_C") (pintype "passive"))
      (node (ref "D4") (pin "C") (pinfunction "C_C") (pintype "passive"))
      (node (ref "D5") (pin "C") (pinfunction "C_C") (pintype "passive"))
      (node (ref "D6") (pin "C") (pinfunction "C_C") (pintype "passive"))
      (node (ref "D7") (pin "C") (pinfunction "C_C") (pintype "passive"))
      (node (ref "D8") (pin "C") (pinfunction "C_C") (pintype "passive"))
      (node (ref "F1") (pin "1") (pinfunction "1_1") (pintype "passive"))
      (node (ref "R20") (pin "2") (pinfunction "2_2") (pintype "passive"))
    )
    (net (code "42") (name "VEXT_VSENSE") (class "Default")
      (node (ref "C14") (pin "1") (pinfunction "C1_1") (pintype "passive"))
      (node (ref "R20") (pin "1") (pinfunction "1_1") (pintype "passive"))
      (node (ref "R22") (pin "2") (pinfunction "2_2") (pintype "passive"))
      (node (ref "U3") (pin "20") (pinfunction "PB12_20") (pintype "bidirectional"))
    )
    (net (code "43") (name "unconnected-(TC1F-S-Pad5)") (class "Default")
      (node (ref "TC1") (pin "5") (pinfunction "S_5") (pintype "passive"))
    )
    (net (code "44") (name "unconnected-(U2-CTS-Pad18)") (class "Default")
      (node (ref "U2") (pin "18") (pinfunction "CTS_18") (pintype "bidirectional"))
    )
    (net (code "45") (name "unconnected-(U2-DCD-Pad24)") (class "Default")
      (node (ref "U2") (pin "24") (pinfunction "DCD_24") (pintype "bidirectional"))
    )
    (net (code "46") (name "unconnected-(U2-DSR-Pad22)") (class "Default")
      (node (ref "U2") (pin "22") (pinfunction "DSR_22") (pintype "bidirectional"))
    )
    (net (code "47") (name "unconnected-(U2-GPIO0-TXT-Pad14)") (class "Default")
      (node (ref "U2") (pin "14") (pinfunction "GPIO0-TXT_14") (pintype "bidirectional"))
    )
    (net (code "48") (name "unconnected-(U2-GPIO1-RXT-Pad13)") (class "Default")
      (node (ref "U2") (pin "13") (pinfunction "GPIO1-RXT_13") (pintype "bidirectional"))
    )
    (net (code "49") (name "unconnected-(U2-GPIO2-RS485-Pad12)") (class "Default")
      (node (ref "U2") (pin "12") (pinfunction "GPIO2-RS485_12") (pintype "bidirectional"))
    )
    (net (code "50") (name "unconnected-(U2-GPIO3-WKUP-Pad11)") (class "Default")
      (node (ref "U2") (pin "11") (pinfunction "GPIO3-WKUP_11") (pintype "bidirectional"))
    )
    (net (code "51") (name "unconnected-(U2-RI{slash}CLK-Pad1)") (class "Default")
      (node (ref "U2") (pin "1") (pinfunction "RI/CLK_1") (pintype "bidirectional"))
    )
    (net (code "52") (name "unconnected-(U2-RTS-Pad19)") (class "Default")
      (node (ref "U2") (pin "19") (pinfunction "RTS_19") (pintype "bidirectional"))
    )
    (net (code "53") (name "unconnected-(U2-SUSPEND-Pad17)") (class "Default")
      (node (ref "U2") (pin "17") (pinfunction "SUSPEND_17") (pintype "bidirectional"))
    )
    (net (code "54") (name "unconnected-(U2-~{SUSPEND}-Pad15)") (class "Default")
      (node (ref "U2") (pin "15") (pinfunction "~{SUSPEND}_15") (pintype "bidirectional"))
    )
    (net (code "55") (name "unconnected-(U3-HFXTAL_N-Pad7)") (class "Default")
      (node (ref "U3") (pin "7") (pinfunction "HFXTAL_N_7") (pintype "bidirectional"))
    )
    (net (code "56") (name "unconnected-(U3-HFXTAL_P-Pad8)") (class "Default")
      (node (ref "U3") (pin "8") (pinfunction "HFXTAL_P_8") (pintype "bidirectional"))
    )
    (net (code "57") (name "unconnected-(U3-PB11-Pad19)") (class "Default")
      (node (ref "U3") (pin "19") (pinfunction "PB11_19") (pintype "bidirectional"))
    )
    (net (code "58") (name "unconnected-(U3-PB13-Pad21)") (class "Default")
      (node (ref "U3") (pin "21") (pinfunction "PB13_21") (pintype "bidirectional"))
    )
    (net (code "59") (name "unconnected-(U3-PB14-Pad23)") (class "Default")
      (node (ref "U3") (pin "23") (pinfunction "PB14_23") (pintype "bidirectional"))
    )
    (net (code "60") (name "unconnected-(U3-PC7-Pad28)") (class "Default")
      (node (ref "U3") (pin "28") (pinfunction "PC7_28") (pintype "bidirectional"))
    )
    (net (code "61") (name "unconnected-(U3-PD12-Pad13)") (class "Default")
      (node (ref "U3") (pin "13") (pinfunction "PD12_13") (pintype "bidirectional"))
    )
    (net (code "62") (name "unconnected-(U3-PD14-Pad15)") (class "Default")
      (node (ref "U3") (pin "15") (pinfunction "PD14_15") (pintype "bidirectional"))
    )
    (net (code "63") (name "unconnected-(U3-PD15-Pad16)") (class "Default")
      (node (ref "U3") (pin "16") (pinfunction "PD15_16") (pintype "bidirectional"))
    )
  )
)
